# peaks_v30.net
KiCad netlist of a schematic drawn in EAGLE
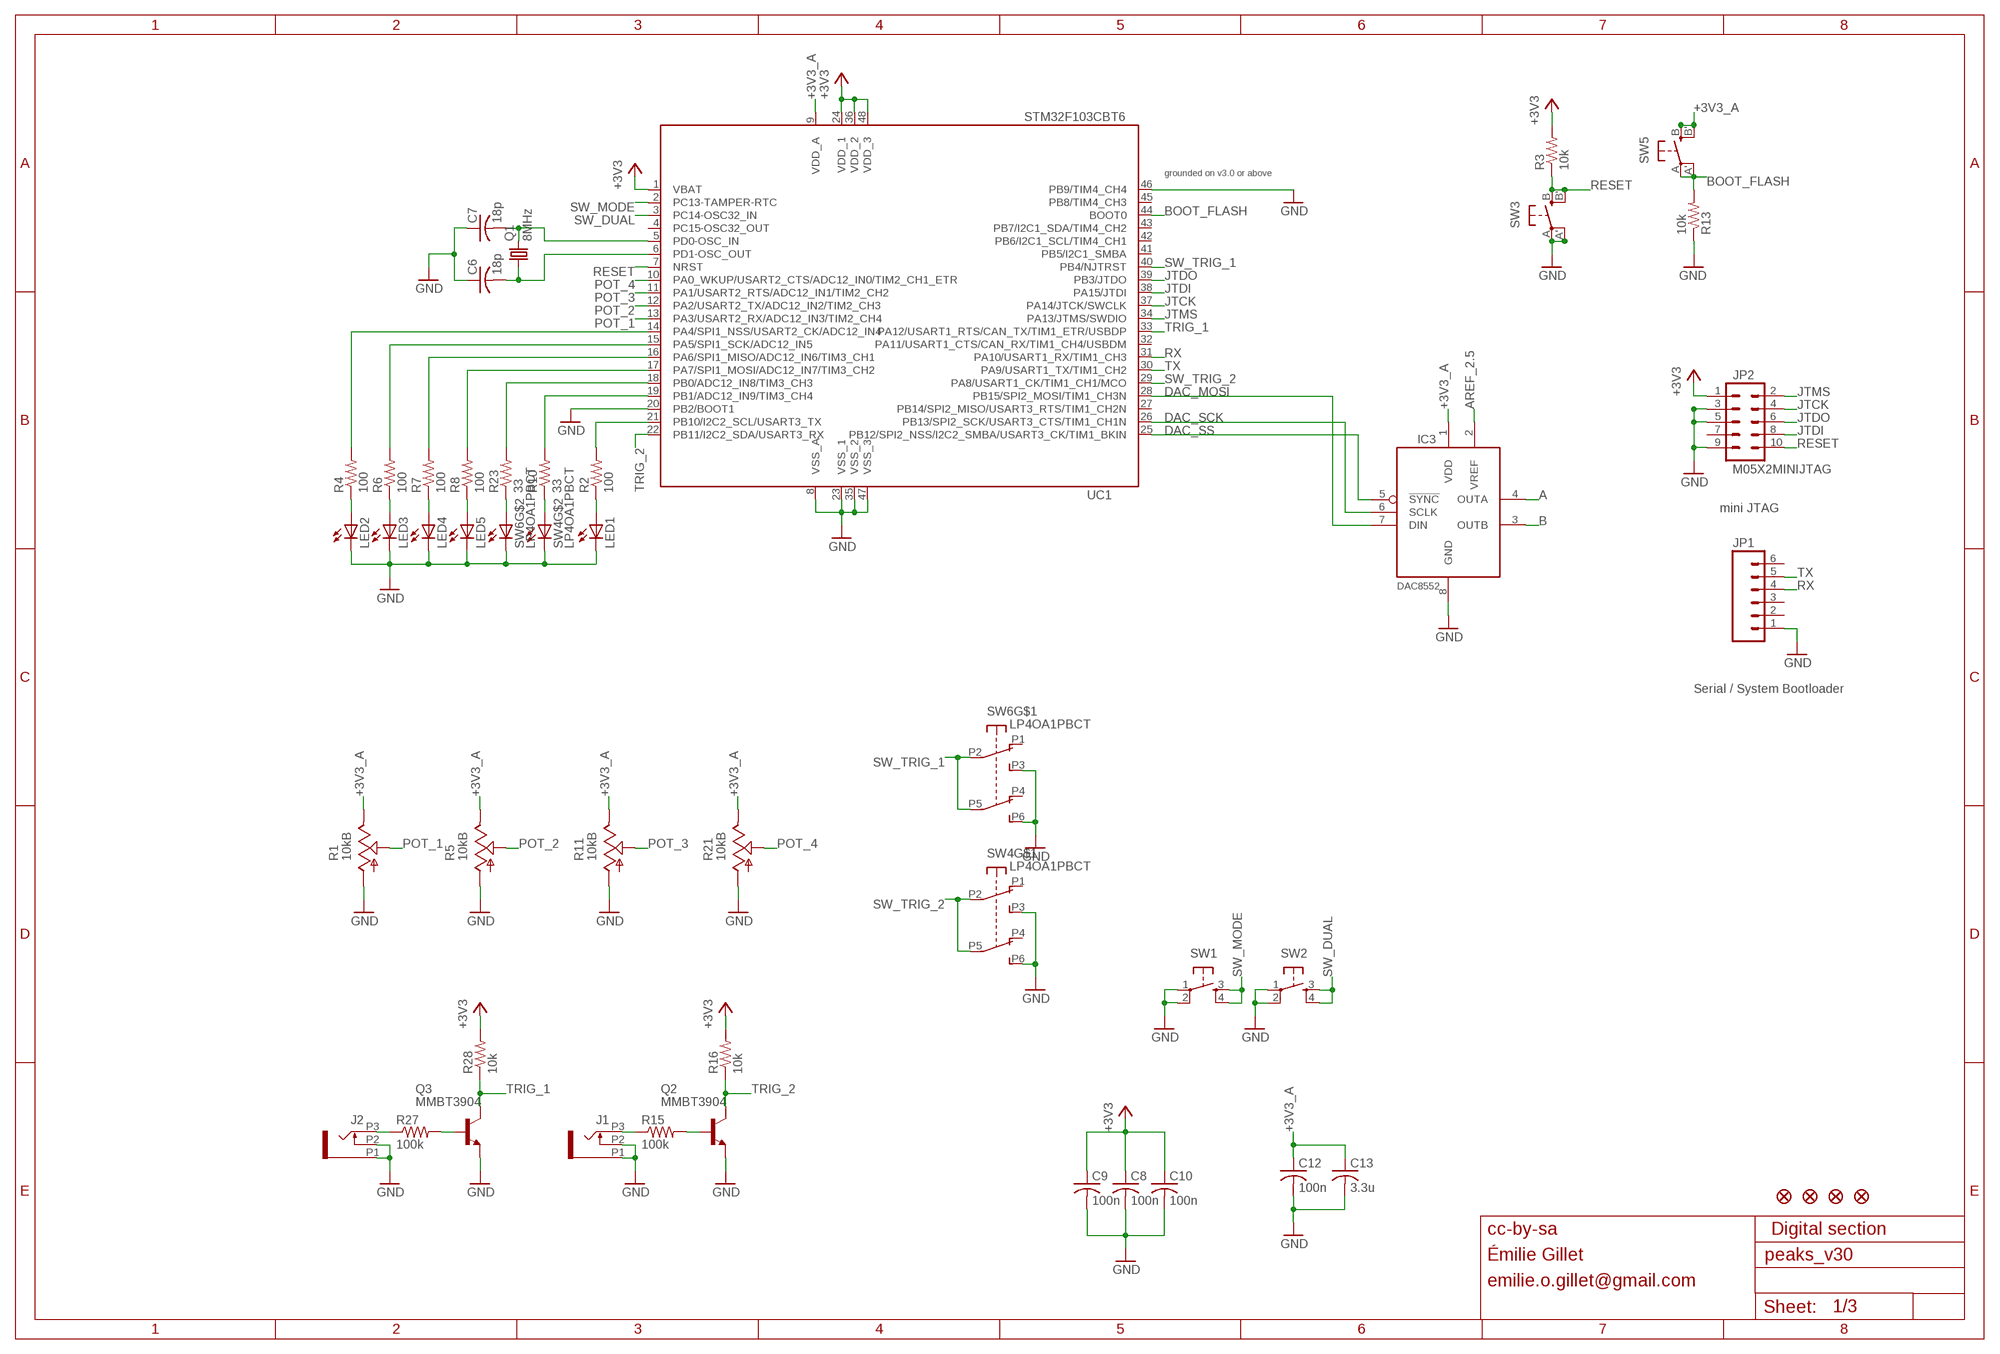
[diagram p0: schematic, sheet 1]
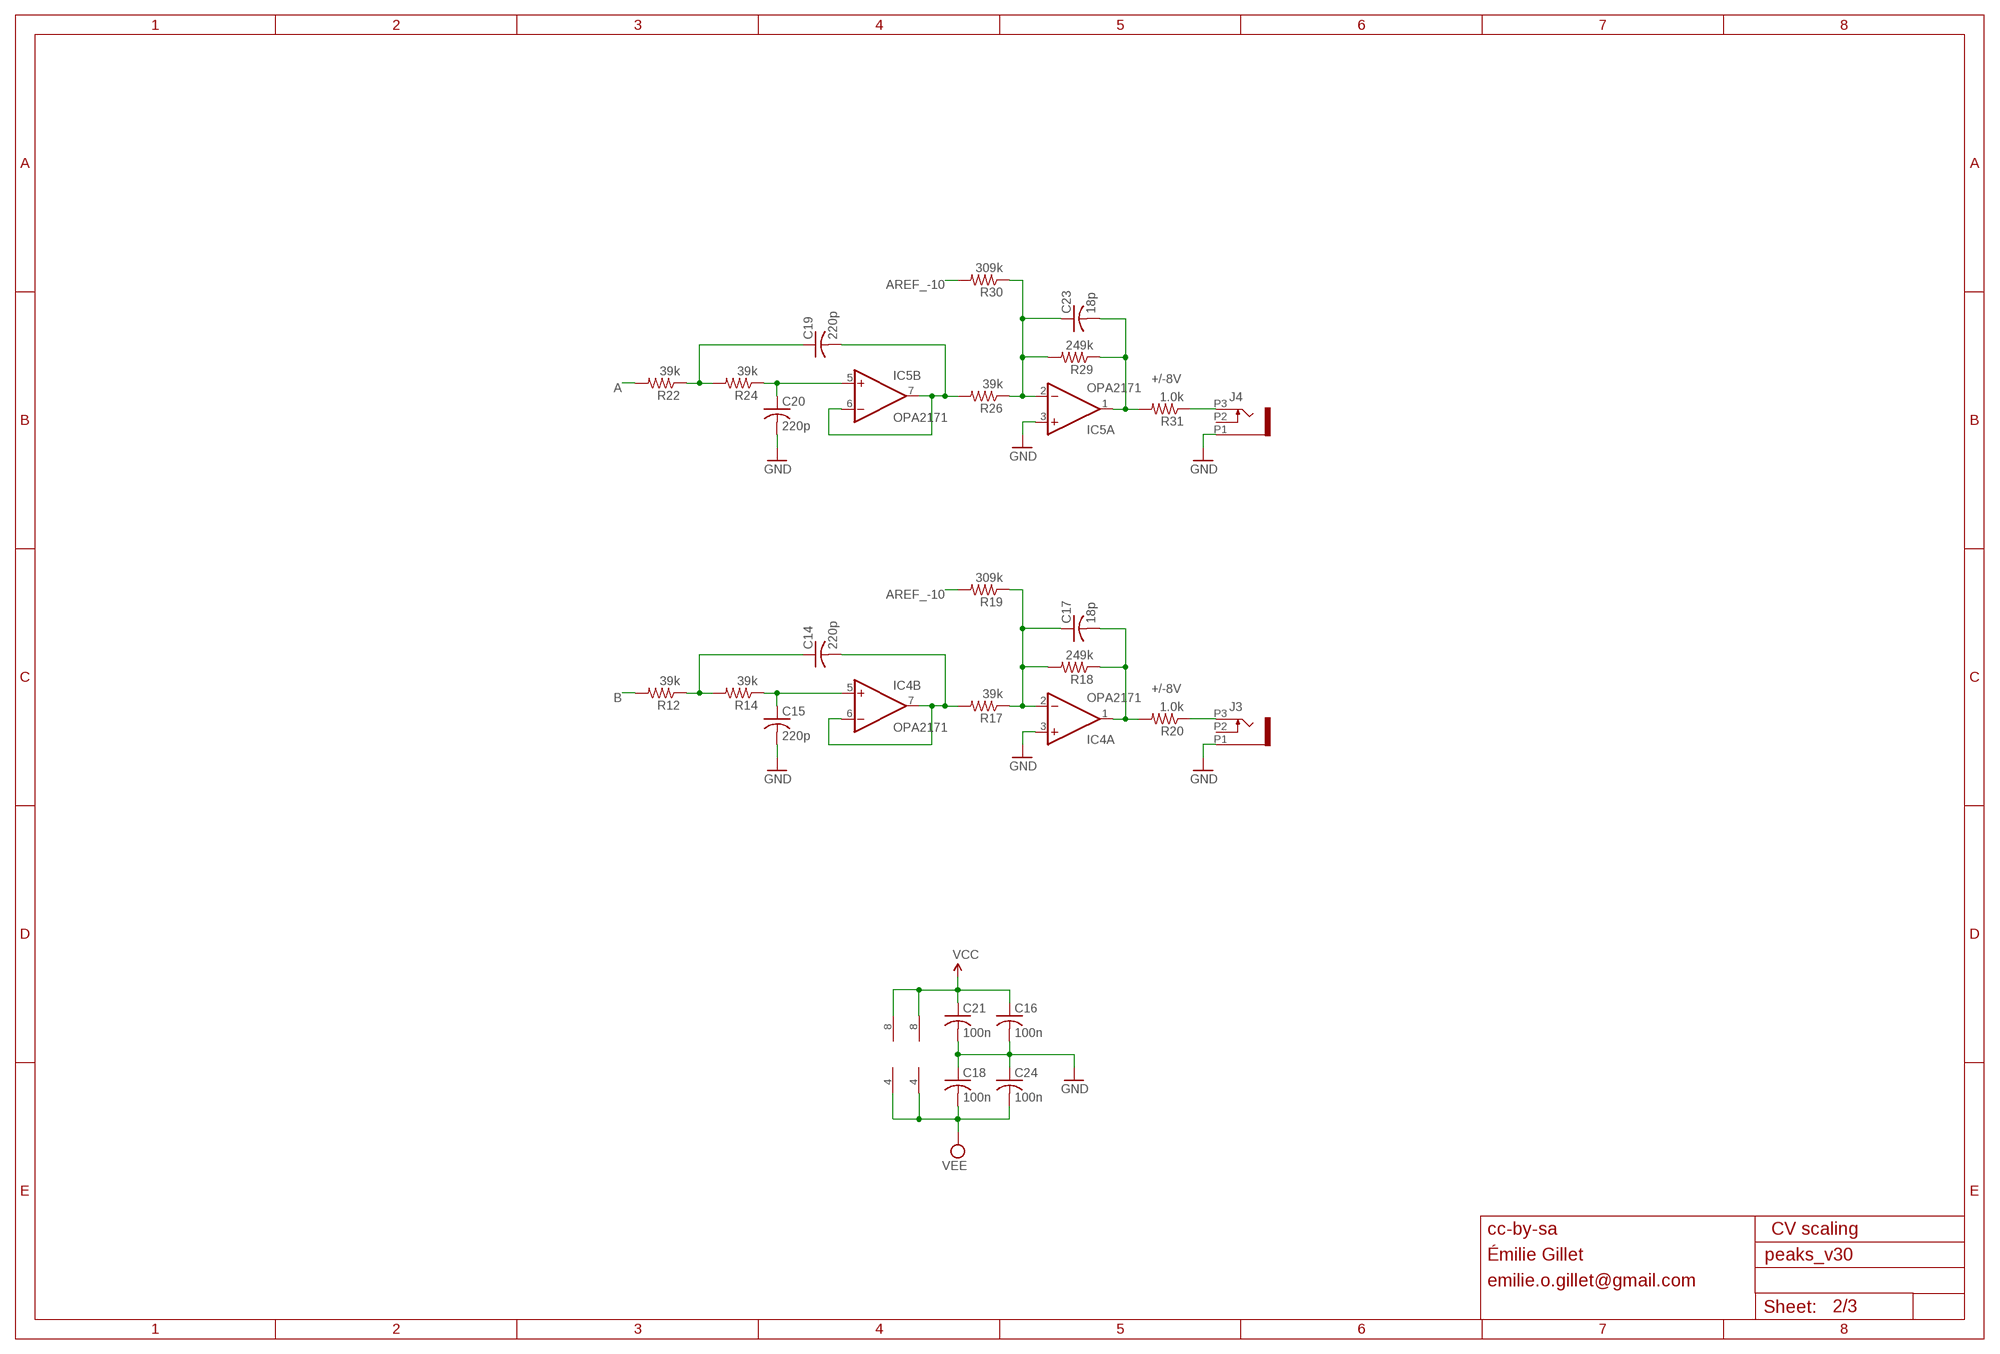
[diagram p1: schematic, sheet 2]
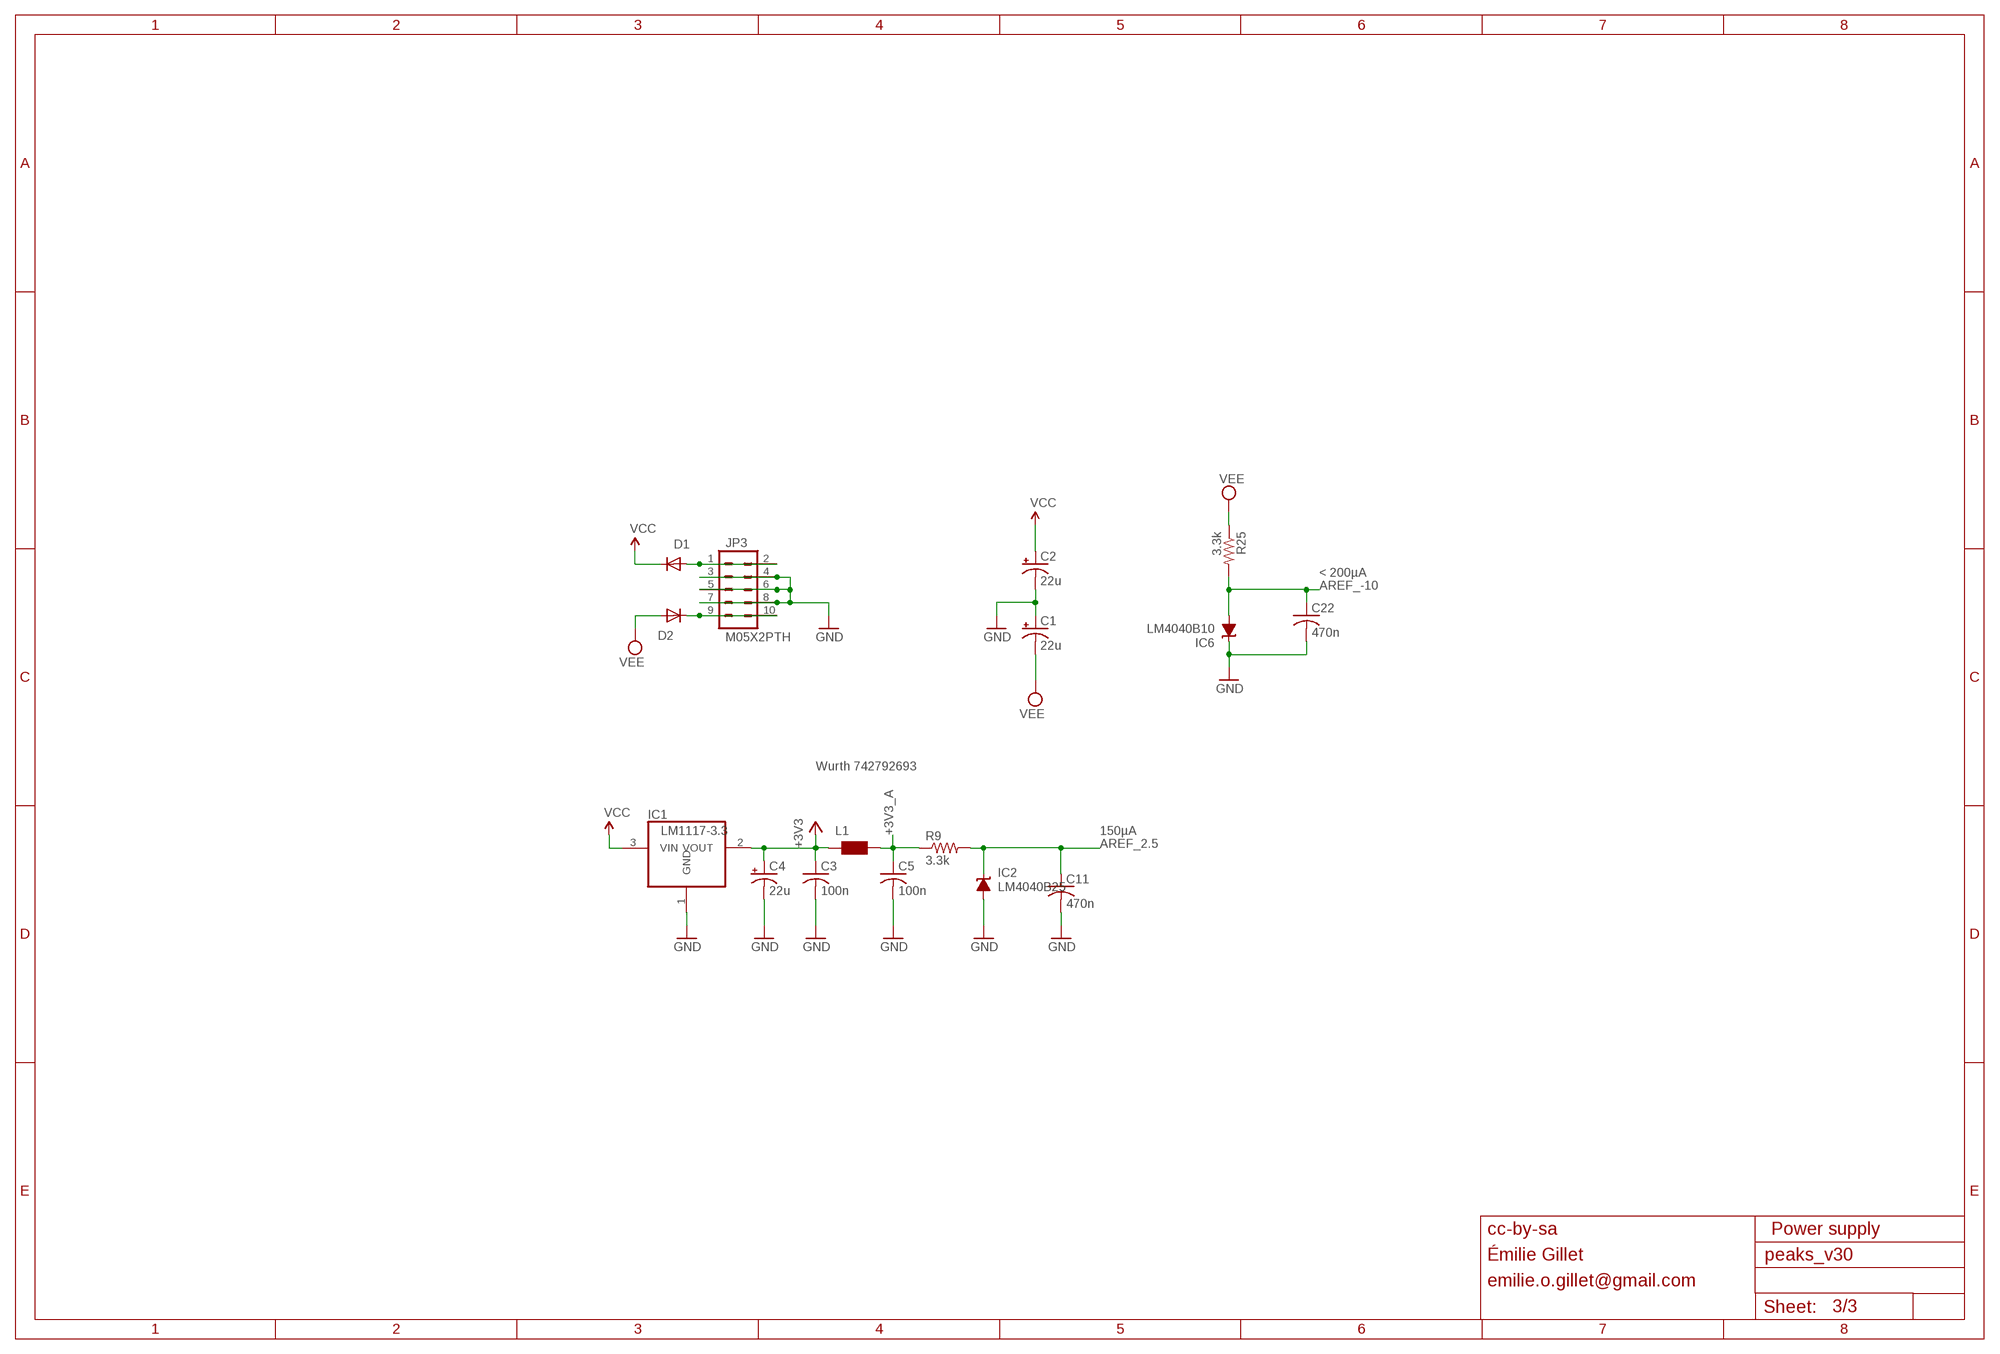
[diagram p2: schematic, sheet 3]

(export (version "E")
  (design (tool "Eeschema 10.0.6"))
  (components
    (comp (ref "C6")
      (value "18p")
      (footprint "eagle-import:C0603")
      (libsource (lib "eagle-import") (part "C-USC0603"))
    )
    (comp (ref "C7")
      (value "18p")
      (footprint "eagle-import:C0603")
      (libsource (lib "eagle-import") (part "C-USC0603"))
    )
    (comp (ref "C8")
      (value "100n")
      (footprint "eagle-import:C0603")
      (libsource (lib "eagle-import") (part "C-USC0603"))
    )
    (comp (ref "C9")
      (value "100n")
      (footprint "eagle-import:C0603")
      (libsource (lib "eagle-import") (part "C-USC0603"))
    )
    (comp (ref "C10")
      (value "100n")
      (footprint "eagle-import:C0603")
      (libsource (lib "eagle-import") (part "C-USC0603"))
    )
    (comp (ref "C12")
      (value "100n")
      (footprint "eagle-import:C0603")
      (libsource (lib "eagle-import") (part "C-USC0603"))
    )
    (comp (ref "C13")
      (value "3.3u")
      (footprint "eagle-import:C0603")
      (libsource (lib "eagle-import") (part "C-USC0603"))
    )
    (comp (ref "F1")
      (value "FIDUCIAL1X2")
      (footprint "eagle-import:FIDUCIAL-1X2")
      (libsource (lib "eagle-import") (part "FIDUCIAL1X2"))
    )
    (comp (ref "F2")
      (value "FIDUCIAL1X2")
      (footprint "eagle-import:FIDUCIAL-1X2")
      (libsource (lib "eagle-import") (part "FIDUCIAL1X2"))
    )
    (comp (ref "F3")
      (value "FIDUCIAL1X2")
      (footprint "eagle-import:FIDUCIAL-1X2")
      (libsource (lib "eagle-import") (part "FIDUCIAL1X2"))
    )
    (comp (ref "F4")
      (value "FIDUCIAL1X2")
      (footprint "eagle-import:FIDUCIAL-1X2")
      (libsource (lib "eagle-import") (part "FIDUCIAL1X2"))
    )
    (comp (ref "IC3")
      (value "DAC8552")
      (footprint "eagle-import:MSOP-8")
      (libsource (lib "eagle-import") (part "DAC8552"))
    )
    (comp (ref "J1")
      (value "PJ301_THONKICONN6")
      (footprint "eagle-import:WQP_PJ_301M6")
      (libsource (lib "eagle-import") (part "PJ301_THONKICONN6"))
    )
    (comp (ref "J2")
      (value "PJ301_THONKICONN6")
      (footprint "eagle-import:WQP_PJ_301M6")
      (libsource (lib "eagle-import") (part "PJ301_THONKICONN6"))
    )
    (comp (ref "JP1")
      (value "M06SIP")
      (footprint "eagle-import:1X06")
      (libsource (lib "eagle-import") (part "M06SIP"))
    )
    (comp (ref "JP2")
      (value "M05X2MINIJTAG")
      (footprint "eagle-import:2X5-1.27")
      (libsource (lib "eagle-import") (part "M05X2MINIJTAG"))
    )
    (comp (ref "LED1")
      (value "LED3MM")
      (footprint "eagle-import:LED3MM")
      (libsource (lib "eagle-import") (part "LED3MM"))
    )
    (comp (ref "LED2")
      (value "LED3MM")
      (footprint "eagle-import:LED3MM")
      (libsource (lib "eagle-import") (part "LED3MM"))
    )
    (comp (ref "LED3")
      (value "LED3MM")
      (footprint "eagle-import:LED3MM")
      (libsource (lib "eagle-import") (part "LED3MM"))
    )
    (comp (ref "LED4")
      (value "LED3MM")
      (footprint "eagle-import:LED3MM")
      (libsource (lib "eagle-import") (part "LED3MM"))
    )
    (comp (ref "LED5")
      (value "LED3MM")
      (footprint "eagle-import:LED3MM")
      (libsource (lib "eagle-import") (part "LED3MM"))
    )
    (comp (ref "Q1")
      (value "8MHz")
      (footprint "eagle-import:HC49UP")
      (libsource (lib "eagle-import") (part "CRYSTALHC49UP"))
    )
    (comp (ref "Q2")
      (value "MMBT3904")
      (footprint "eagle-import:SOT23-BEC")
      (libsource (lib "eagle-import") (part "-NPN-SOT23-BECMMBT3904LT1"))
    )
    (comp (ref "Q3")
      (value "MMBT3904")
      (footprint "eagle-import:SOT23-BEC")
      (libsource (lib "eagle-import") (part "-NPN-SOT23-BECMMBT3904LT1"))
    )
    (comp (ref "R1")
      (value "10kB")
      (footprint "eagle-import:ALPS_POT_VERTICAL_PS")
      (libsource (lib "eagle-import") (part "POT_USVERTICAL_PS"))
    )
    (comp (ref "R2")
      (value "100")
      (footprint "eagle-import:R0603")
      (libsource (lib "eagle-import") (part "R-US_R0603"))
    )
    (comp (ref "R3")
      (value "10k")
      (footprint "eagle-import:R0603")
      (libsource (lib "eagle-import") (part "R-US_R0603"))
    )
    (comp (ref "R4")
      (value "100")
      (footprint "eagle-import:R0603")
      (libsource (lib "eagle-import") (part "R-US_R0603"))
    )
    (comp (ref "R5")
      (value "10kB")
      (footprint "eagle-import:ALPS_POT_VERTICAL_PS")
      (libsource (lib "eagle-import") (part "POT_USVERTICAL_PS"))
    )
    (comp (ref "R6")
      (value "100")
      (footprint "eagle-import:R0603")
      (libsource (lib "eagle-import") (part "R-US_R0603"))
    )
    (comp (ref "R7")
      (value "100")
      (footprint "eagle-import:R0603")
      (libsource (lib "eagle-import") (part "R-US_R0603"))
    )
    (comp (ref "R8")
      (value "100")
      (footprint "eagle-import:R0603")
      (libsource (lib "eagle-import") (part "R-US_R0603"))
    )
    (comp (ref "R10")
      (value "33")
      (footprint "eagle-import:R0603")
      (libsource (lib "eagle-import") (part "R-US_R0603"))
    )
    (comp (ref "R11")
      (value "10kB")
      (footprint "eagle-import:ALPS_POT_VERTICAL_PS")
      (libsource (lib "eagle-import") (part "POT_USVERTICAL_PS"))
    )
    (comp (ref "R13")
      (value "10k")
      (footprint "eagle-import:R0603")
      (libsource (lib "eagle-import") (part "R-US_R0603"))
    )
    (comp (ref "R15")
      (value "100k")
      (footprint "eagle-import:R0603")
      (libsource (lib "eagle-import") (part "R-US_R0603"))
    )
    (comp (ref "R16")
      (value "10k")
      (footprint "eagle-import:R0603")
      (libsource (lib "eagle-import") (part "R-US_R0603"))
    )
    (comp (ref "R21")
      (value "10kB")
      (footprint "eagle-import:ALPS_POT_VERTICAL_PS")
      (libsource (lib "eagle-import") (part "POT_USVERTICAL_PS"))
    )
    (comp (ref "R23")
      (value "33")
      (footprint "eagle-import:R0603")
      (libsource (lib "eagle-import") (part "R-US_R0603"))
    )
    (comp (ref "R27")
      (value "100k")
      (footprint "eagle-import:R0603")
      (libsource (lib "eagle-import") (part "R-US_R0603"))
    )
    (comp (ref "R28")
      (value "10k")
      (footprint "eagle-import:R0603")
      (libsource (lib "eagle-import") (part "R-US_R0603"))
    )
    (comp (ref "SW1")
      (value "TAC_SWITCHPTH")
      (footprint "eagle-import:TACTILE-PTH")
      (libsource (lib "eagle-import") (part "TAC_SWITCHPTH"))
    )
    (comp (ref "SW2")
      (value "TAC_SWITCHPTH")
      (footprint "eagle-import:TACTILE-PTH")
      (libsource (lib "eagle-import") (part "TAC_SWITCHPTH"))
    )
    (comp (ref "SW3")
      (value "EVQQ2")
      (footprint "eagle-import:EVQ-Q2")
      (libsource (lib "eagle-import") (part "EVQQ2"))
    )
    (comp (ref "SW4")
      (value "LP4OA1PBCT")
      (footprint "eagle-import:LP4OA1PBCT")
      (libsource (lib "eagle-import") (part "LP4OA1PBCT"))
    )
    (comp (ref "SW5")
      (value "EVQQ2")
      (footprint "eagle-import:EVQ-Q2")
      (libsource (lib "eagle-import") (part "EVQQ2"))
    )
    (comp (ref "SW6")
      (value "LP4OA1PBCT")
      (footprint "eagle-import:LP4OA1PBCT")
      (libsource (lib "eagle-import") (part "LP4OA1PBCT"))
    )
    (comp (ref "UC1")
      (value "STM32F103CBT6")
      (footprint "eagle-import:LQFP48")
      (libsource (lib "eagle-import") (part "STM32F103CB"))
    )
    (comp (ref "C14")
      (value "220p")
      (footprint "eagle-import:C0603")
      (libsource (lib "eagle-import") (part "C-USC0603"))
    )
    (comp (ref "C15")
      (value "220p")
      (footprint "eagle-import:C0603")
      (libsource (lib "eagle-import") (part "C-USC0603"))
    )
    (comp (ref "C16")
      (value "100n")
      (footprint "eagle-import:C0603")
      (libsource (lib "eagle-import") (part "C-USC0603"))
    )
    (comp (ref "C17")
      (value "18p")
      (footprint "eagle-import:C0603")
      (libsource (lib "eagle-import") (part "C-USC0603"))
    )
    (comp (ref "C18")
      (value "100n")
      (footprint "eagle-import:C0603")
      (libsource (lib "eagle-import") (part "C-USC0603"))
    )
    (comp (ref "C19")
      (value "220p")
      (footprint "eagle-import:C0603")
      (libsource (lib "eagle-import") (part "C-USC0603"))
    )
    (comp (ref "C20")
      (value "220p")
      (footprint "eagle-import:C0603")
      (libsource (lib "eagle-import") (part "C-USC0603"))
    )
    (comp (ref "C21")
      (value "100n")
      (footprint "eagle-import:C0603")
      (libsource (lib "eagle-import") (part "C-USC0603"))
    )
    (comp (ref "C23")
      (value "18p")
      (footprint "eagle-import:C0603")
      (libsource (lib "eagle-import") (part "C-USC0603"))
    )
    (comp (ref "C24")
      (value "100n")
      (footprint "eagle-import:C0603")
      (libsource (lib "eagle-import") (part "C-USC0603"))
    )
    (comp (ref "IC4")
      (value "OPA2171")
      (footprint "eagle-import:SO08")
      (libsource (lib "eagle-import") (part "TL072D"))
    )
    (comp (ref "IC5")
      (value "OPA2171")
      (footprint "eagle-import:SO08")
      (libsource (lib "eagle-import") (part "TL072D"))
    )
    (comp (ref "J3")
      (value "PJ301_THONKICONN6")
      (footprint "eagle-import:WQP_PJ_301M6")
      (libsource (lib "eagle-import") (part "PJ301_THONKICONN6"))
    )
    (comp (ref "J4")
      (value "PJ301_THONKICONN6")
      (footprint "eagle-import:WQP_PJ_301M6")
      (libsource (lib "eagle-import") (part "PJ301_THONKICONN6"))
    )
    (comp (ref "R12")
      (value "39k")
      (footprint "eagle-import:R0603")
      (libsource (lib "eagle-import") (part "R-US_R0603"))
    )
    (comp (ref "R14")
      (value "39k")
      (footprint "eagle-import:R0603")
      (libsource (lib "eagle-import") (part "R-US_R0603"))
    )
    (comp (ref "R17")
      (value "39k")
      (footprint "eagle-import:R0603")
      (libsource (lib "eagle-import") (part "R-US_R0603"))
    )
    (comp (ref "R18")
      (value "249k")
      (footprint "eagle-import:R0603")
      (libsource (lib "eagle-import") (part "R-US_R0603"))
    )
    (comp (ref "R19")
      (value "309k")
      (footprint "eagle-import:R0603")
      (libsource (lib "eagle-import") (part "R-US_R0603"))
    )
    (comp (ref "R20")
      (value "1.0k")
      (footprint "eagle-import:R0603")
      (libsource (lib "eagle-import") (part "R-US_R0603"))
    )
    (comp (ref "R22")
      (value "39k")
      (footprint "eagle-import:R0603")
      (libsource (lib "eagle-import") (part "R-US_R0603"))
    )
    (comp (ref "R24")
      (value "39k")
      (footprint "eagle-import:R0603")
      (libsource (lib "eagle-import") (part "R-US_R0603"))
    )
    (comp (ref "R26")
      (value "39k")
      (footprint "eagle-import:R0603")
      (libsource (lib "eagle-import") (part "R-US_R0603"))
    )
    (comp (ref "R29")
      (value "249k")
      (footprint "eagle-import:R0603")
      (libsource (lib "eagle-import") (part "R-US_R0603"))
    )
    (comp (ref "R30")
      (value "309k")
      (footprint "eagle-import:R0603")
      (libsource (lib "eagle-import") (part "R-US_R0603"))
    )
    (comp (ref "R31")
      (value "1.0k")
      (footprint "eagle-import:R0603")
      (libsource (lib "eagle-import") (part "R-US_R0603"))
    )
    (comp (ref "C1")
      (value "22u")
      (footprint "eagle-import:PANASONIC_C")
      (libsource (lib "eagle-import") (part "CPOL-USC"))
    )
    (comp (ref "C2")
      (value "22u")
      (footprint "eagle-import:PANASONIC_C")
      (libsource (lib "eagle-import") (part "CPOL-USC"))
    )
    (comp (ref "C3")
      (value "100n")
      (footprint "eagle-import:C0603")
      (libsource (lib "eagle-import") (part "C-USC0603"))
    )
    (comp (ref "C4")
      (value "22u")
      (footprint "eagle-import:PANASONIC_C")
      (libsource (lib "eagle-import") (part "CPOL-USC"))
    )
    (comp (ref "C5")
      (value "100n")
      (footprint "eagle-import:C0603")
      (libsource (lib "eagle-import") (part "C-USC0603"))
    )
    (comp (ref "C11")
      (value "470n")
      (footprint "eagle-import:C0603")
      (libsource (lib "eagle-import") (part "C-USC0603"))
    )
    (comp (ref "C22")
      (value "470n")
      (footprint "eagle-import:C0603")
      (libsource (lib "eagle-import") (part "C-USC0603"))
    )
    (comp (ref "D1")
      (value "1N5819HW")
      (footprint "eagle-import:SOD123")
      (libsource (lib "eagle-import") (part "DIODE-SOD123"))
    )
    (comp (ref "D2")
      (value "1N5819HW")
      (footprint "eagle-import:SOD123")
      (libsource (lib "eagle-import") (part "DIODE-SOD123"))
    )
    (comp (ref "IC1")
      (value "LM1117-3.3")
      (footprint "eagle-import:SOT223")
      (libsource (lib "eagle-import") (part "REG1117"))
    )
    (comp (ref "IC2")
      (value "LM4040B25")
      (footprint "eagle-import:DBZ_R-PDSO-G3")
      (libsource (lib "eagle-import") (part "LM4041DBZB12"))
    )
    (comp (ref "IC6")
      (value "LM4040B10")
      (footprint "eagle-import:DBZ_R-PDSO-G3")
      (libsource (lib "eagle-import") (part "LM4041DBZB12"))
    )
    (comp (ref "JP3")
      (value "M05X2PTH")
      (footprint "eagle-import:AVR_ICSP")
      (libsource (lib "eagle-import") (part "M05X2PTH"))
    )
    (comp (ref "L1")
      (value "WE-CBF_0603")
      (footprint "eagle-import:0603")
      (libsource (lib "eagle-import") (part "WE-CBF_0603"))
    )
    (comp (ref "R9")
      (value "3.3k")
      (footprint "eagle-import:R0603")
      (libsource (lib "eagle-import") (part "R-US_R0603"))
    )
    (comp (ref "R25")
      (value "3.3k")
      (footprint "eagle-import:R0603")
      (libsource (lib "eagle-import") (part "R-US_R0603"))
    )
  )
  (nets
    (net (code "1") (name "+3V3") (class "Default")
      (node (ref "C10") (pin "1") (pinfunction "1_1") (pintype "passive"))
      (node (ref "C3") (pin "1") (pinfunction "1_1") (pintype "passive"))
      (node (ref "C4") (pin "+") (pinfunction "+_+") (pintype "passive"))
      (node (ref "C8") (pin "1") (pinfunction "1_1") (pintype "passive"))
      (node (ref "C9") (pin "1") (pinfunction "1_1") (pintype "passive"))
      (node (ref "IC1") (pin "2") (pinfunction "VOUT_2") (pintype "output"))
      (node (ref "JP2") (pin "1") (pinfunction "1_1") (pintype "passive"))
      (node (ref "L1") (pin "1") (pinfunction "1_1") (pintype "passive"))
      (node (ref "R16") (pin "2") (pinfunction "2_2") (pintype "passive"))
      (node (ref "R28") (pin "2") (pinfunction "2_2") (pintype "passive"))
      (node (ref "R3") (pin "2") (pinfunction "2_2") (pintype "passive"))
      (node (ref "UC1") (pin "1") (pinfunction "VBAT_1") (pintype "power_in"))
      (node (ref "UC1") (pin "24") (pinfunction "VDD_1_24") (pintype "power_in"))
      (node (ref "UC1") (pin "36") (pinfunction "VDD_2_36") (pintype "power_in"))
      (node (ref "UC1") (pin "48") (pinfunction "VDD_3_48") (pintype "power_in"))
    )
    (net (code "2") (name "+3V3_A") (class "Default")
      (node (ref "C12") (pin "1") (pinfunction "1_1") (pintype "passive"))
      (node (ref "C13") (pin "1") (pinfunction "1_1") (pintype "passive"))
      (node (ref "C5") (pin "1") (pinfunction "1_1") (pintype "passive"))
      (node (ref "IC3") (pin "1") (pinfunction "VDD_1") (pintype "power_in"))
      (node (ref "L1") (pin "2") (pinfunction "2_2") (pintype "passive"))
      (node (ref "R1") (pin "P$1") (pinfunction "E_P$1") (pintype "passive"))
      (node (ref "R11") (pin "P$1") (pinfunction "E_P$1") (pintype "passive"))
      (node (ref "R21") (pin "P$1") (pinfunction "E_P$1") (pintype "passive"))
      (node (ref "R5") (pin "P$1") (pinfunction "E_P$1") (pintype "passive"))
      (node (ref "R9") (pin "1") (pinfunction "1_1") (pintype "passive"))
      (node (ref "SW5") (pin "B") (pinfunction "S_B") (pintype "passive"))
      (node (ref "SW5") (pin "B'") (pinfunction "S1_B'") (pintype "passive"))
      (node (ref "UC1") (pin "9") (pinfunction "VDD_A_9") (pintype "power_in"))
    )
    (net (code "3") (name "A") (class "Default")
      (node (ref "IC3") (pin "4") (pinfunction "OUTA_4") (pintype "output"))
      (node (ref "R22") (pin "2") (pinfunction "2_2") (pintype "passive"))
    )
    (net (code "4") (name "AREF_-10") (class "Default")
      (node (ref "C22") (pin "1") (pinfunction "1_1") (pintype "passive"))
      (node (ref "IC6") (pin "2") (pinfunction "A_2") (pintype "passive"))
      (node (ref "R19") (pin "2") (pinfunction "2_2") (pintype "passive"))
      (node (ref "R25") (pin "2") (pinfunction "2_2") (pintype "passive"))
      (node (ref "R30") (pin "2") (pinfunction "2_2") (pintype "passive"))
    )
    (net (code "5") (name "AREF_2.5") (class "Default")
      (node (ref "C11") (pin "1") (pinfunction "1_1") (pintype "passive"))
      (node (ref "IC2") (pin "1") (pinfunction "C_1") (pintype "passive"))
      (node (ref "IC3") (pin "2") (pinfunction "VREF_2") (pintype "power_in"))
      (node (ref "R9") (pin "2") (pinfunction "2_2") (pintype "passive"))
    )
    (net (code "6") (name "B") (class "Default")
      (node (ref "IC3") (pin "3") (pinfunction "OUTB_3") (pintype "input"))
      (node (ref "R12") (pin "2") (pinfunction "2_2") (pintype "passive"))
    )
    (net (code "7") (name "BOOT_FLASH") (class "Default")
      (node (ref "R13") (pin "2") (pinfunction "2_2") (pintype "passive"))
      (node (ref "SW5") (pin "A") (pinfunction "P_A") (pintype "passive"))
      (node (ref "SW5") (pin "A'") (pinfunction "P1_A'") (pintype "passive"))
      (node (ref "UC1") (pin "44") (pinfunction "BOOT0_44") (pintype "input"))
    )
    (net (code "8") (name "DAC_MOSI") (class "Default")
      (node (ref "IC3") (pin "7") (pinfunction "DIN_7") (pintype "bidirectional"))
      (node (ref "UC1") (pin "28") (pinfunction "PB15/SPI2_MOSI/TIM1_CH3N_28") (pintype "input"))
    )
    (net (code "9") (name "DAC_SCK") (class "Default")
      (node (ref "IC3") (pin "6") (pinfunction "SCLK_6") (pintype "bidirectional"))
      (node (ref "UC1") (pin "26") (pinfunction "PB13/SPI2_SCK/USART3_CTS/TIM1_CH1N_26") (pintype "input"))
    )
    (net (code "10") (name "DAC_SS") (class "Default")
      (node (ref "IC3") (pin "5") (pinfunction "~{SYNC}_5") (pintype "bidirectional"))
      (node (ref "UC1") (pin "25") (pinfunction "PB12/SPI2_NSS/I2C2_SMBA/USART3_CK/TIM1_BKIN_25") (pintype "input"))
    )
    (net (code "11") (name "GND") (class "Default")
      (node (ref "C1") (pin "+") (pinfunction "+_+") (pintype "passive"))
      (node (ref "C10") (pin "2") (pinfunction "2_2") (pintype "passive"))
      (node (ref "C11") (pin "2") (pinfunction "2_2") (pintype "passive"))
      (node (ref "C12") (pin "2") (pinfunction "2_2") (pintype "passive"))
      (node (ref "C13") (pin "2") (pinfunction "2_2") (pintype "passive"))
      (node (ref "C15") (pin "2") (pinfunction "2_2") (pintype "passive"))
      (node (ref "C16") (pin "2") (pinfunction "2_2") (pintype "passive"))
      (node (ref "C18") (pin "1") (pinfunction "1_1") (pintype "passive"))
      (node (ref "C2") (pin "-") (pinfunction "-_-") (pintype "passive"))
      (node (ref "C20") (pin "2") (pinfunction "2_2") (pintype "passive"))
      (node (ref "C21") (pin "2") (pinfunction "2_2") (pintype "passive"))
      (node (ref "C22") (pin "2") (pinfunction "2_2") (pintype "passive"))
      (node (ref "C24") (pin "1") (pinfunction "1_1") (pintype "passive"))
      (node (ref "C3") (pin "2") (pinfunction "2_2") (pintype "passive"))
      (node (ref "C4") (pin "-") (pinfunction "-_-") (pintype "passive"))
      (node (ref "C5") (pin "2") (pinfunction "2_2") (pintype "passive"))
      (node (ref "C6") (pin "1") (pinfunction "1_1") (pintype "passive"))
      (node (ref "C7") (pin "1") (pinfunction "1_1") (pintype "passive"))
      (node (ref "C8") (pin "2") (pinfunction "2_2") (pintype "passive"))
      (node (ref "C9") (pin "2") (pinfunction "2_2") (pintype "passive"))
      (node (ref "IC1") (pin "1") (pinfunction "GND_1") (pintype "power_in"))
      (node (ref "IC2") (pin "2") (pinfunction "A_2") (pintype "passive"))
      (node (ref "IC3") (pin "8") (pinfunction "GND_8") (pintype "power_in"))
      (node (ref "IC4") (pin "3") (pinfunction "+IN_3") (pintype "input"))
      (node (ref "IC5") (pin "3") (pinfunction "+IN_3") (pintype "input"))
      (node (ref "IC6") (pin "1") (pinfunction "C_1") (pintype "passive"))
      (node (ref "J1") (pin "P1") (pinfunction "1_P1") (pintype "passive"))
      (node (ref "J1") (pin "P2") (pinfunction "2_P2") (pintype "passive"))
      (node (ref "J2") (pin "P1") (pinfunction "1_P1") (pintype "passive"))
      (node (ref "J2") (pin "P2") (pinfunction "2_P2") (pintype "passive"))
      (node (ref "J3") (pin "P1") (pinfunction "1_P1") (pintype "passive"))
      (node (ref "J4") (pin "P1") (pinfunction "1_P1") (pintype "passive"))
      (node (ref "JP1") (pin "1") (pinfunction "1_1") (pintype "passive"))
      (node (ref "JP2") (pin "3") (pinfunction "3_3") (pintype "passive"))
      (node (ref "JP2") (pin "5") (pinfunction "5_5") (pintype "passive"))
      (node (ref "JP2") (pin "9") (pinfunction "9_9") (pintype "passive"))
      (node (ref "JP3") (pin "3") (pinfunction "3_3") (pintype "passive"))
      (node (ref "JP3") (pin "4") (pinfunction "4_4") (pintype "passive"))
      (node (ref "JP3") (pin "5") (pinfunction "5_5") (pintype "passive"))
      (node (ref "JP3") (pin "6") (pinfunction "6_6") (pintype "passive"))
      (node (ref "JP3") (pin "7") (pinfunction "7_7") (pintype "passive"))
      (node (ref "JP3") (pin "8") (pinfunction "8_8") (pintype "passive"))
      (node (ref "LED1") (pin "K") (pinfunction "C_K") (pintype "passive"))
      (node (ref "LED2") (pin "K") (pinfunction "C_K") (pintype "passive"))
      (node (ref "LED3") (pin "K") (pinfunction "C_K") (pintype "passive"))
      (node (ref "LED4") (pin "K") (pinfunction "C_K") (pintype "passive"))
      (node (ref "LED5") (pin "K") (pinfunction "C_K") (pintype "passive"))
      (node (ref "Q2") (pin "E") (pinfunction "E_E") (pintype "passive"))
      (node (ref "Q3") (pin "E") (pinfunction "E_E") (pintype "passive"))
      (node (ref "R1") (pin "P$3") (pinfunction "A_P$3") (pintype "passive"))
      (node (ref "R11") (pin "P$3") (pinfunction "A_P$3") (pintype "passive"))
      (node (ref "R13") (pin "1") (pinfunction "1_1") (pintype "passive"))
      (node (ref "R21") (pin "P$3") (pinfunction "A_P$3") (pintype "passive"))
      (node (ref "R5") (pin "P$3") (pinfunction "A_P$3") (pintype "passive"))
      (node (ref "SW1") (pin "1") (pinfunction "1_1") (pintype "passive"))
      (node (ref "SW1") (pin "2") (pinfunction "2_2") (pintype "passive"))
      (node (ref "SW2") (pin "1") (pinfunction "1_1") (pintype "passive"))
      (node (ref "SW2") (pin "2") (pinfunction "2_2") (pintype "passive"))
      (node (ref "SW3") (pin "A") (pinfunction "P_A") (pintype "passive"))
      (node (ref "SW3") (pin "A'") (pinfunction "P1_A'") (pintype "passive"))
      (node (ref "SW4") (pin "L2") (pinfunction "L2_L2") (pintype "passive"))
      (node (ref "SW4") (pin "P3") (pinfunction "A3_P3") (pintype "passive"))
      (node (ref "SW4") (pin "P6") (pinfunction "B3_P6") (pintype "passive"))
      (node (ref "SW6") (pin "L2") (pinfunction "L2_L2") (pintype "passive"))
      (node (ref "SW6") (pin "P3") (pinfunction "A3_P3") (pintype "passive"))
      (node (ref "SW6") (pin "P6") (pinfunction "B3_P6") (pintype "passive"))
      (node (ref "UC1") (pin "20") (pinfunction "PB2/BOOT1_20") (pintype "bidirectional"))
      (node (ref "UC1") (pin "23") (pinfunction "VSS_1_23") (pintype "power_in"))
      (node (ref "UC1") (pin "35") (pinfunction "VSS_2_35") (pintype "power_in"))
      (node (ref "UC1") (pin "46") (pinfunction "PB9/TIM4_CH4_46") (pintype "input"))
      (node (ref "UC1") (pin "47") (pinfunction "VSS_3_47") (pintype "power_in"))
      (node (ref "UC1") (pin "8") (pinfunction "VSS_A_8") (pintype "power_in"))
    )
    (net (code "12") (name "JTCK") (class "Default")
      (node (ref "JP2") (pin "4") (pinfunction "4_4") (pintype "passive"))
      (node (ref "UC1") (pin "37") (pinfunction "PA14/JTCK/SWCLK_37") (pintype "bidirectional"))
    )
    (net (code "13") (name "JTDI") (class "Default")
      (node (ref "JP2") (pin "8") (pinfunction "8_8") (pintype "passive"))
      (node (ref "UC1") (pin "38") (pinfunction "PA15/JTDI_38") (pintype "bidirectional"))
    )
    (net (code "14") (name "JTDO") (class "Default")
      (node (ref "JP2") (pin "6") (pinfunction "6_6") (pintype "passive"))
      (node (ref "UC1") (pin "39") (pinfunction "PB3/JTDO_39") (pintype "bidirectional"))
    )
    (net (code "15") (name "JTMS") (class "Default")
      (node (ref "JP2") (pin "2") (pinfunction "2_2") (pintype "passive"))
      (node (ref "UC1") (pin "34") (pinfunction "PA13/JTMS/SWDIO_34") (pintype "bidirectional"))
    )
    (net (code "16") (name "Net-(C14-Pad1)") (class "Default")
      (node (ref "C14") (pin "1") (pinfunction "1_1") (pintype "passive"))
      (node (ref "R12") (pin "1") (pinfunction "1_1") (pintype "passive"))
      (node (ref "R14") (pin "2") (pinfunction "2_2") (pintype "passive"))
    )
    (net (code "17") (name "Net-(C19-Pad1)") (class "Default")
      (node (ref "C19") (pin "1") (pinfunction "1_1") (pintype "passive"))
      (node (ref "R22") (pin "1") (pinfunction "1_1") (pintype "passive"))
      (node (ref "R24") (pin "2") (pinfunction "2_2") (pintype "passive"))
    )
    (net (code "18") (name "Net-(D1-PadA)") (class "Default")
      (node (ref "D1") (pin "A") (pinfunction "A_A") (pintype "passive"))
      (node (ref "JP3") (pin "1") (pinfunction "1_1") (pintype "passive"))
      (node (ref "JP3") (pin "2") (pinfunction "2_2") (pintype "passive"))
    )
    (net (code "19") (name "Net-(D2-PadC)") (class "Default")
      (node (ref "D2") (pin "C") (pinfunction "C_C") (pintype "passive"))
      (node (ref "JP3") (pin "10") (pinfunction "10_10") (pintype "passive"))
      (node (ref "JP3") (pin "9") (pinfunction "9_9") (pintype "passive"))
    )
    (net (code "20") (name "Net-(IC4A--IN)") (class "Default")
      (node (ref "C17") (pin "1") (pinfunction "1_1") (pintype "passive"))
      (node (ref "IC4") (pin "2") (pinfunction "-IN_2") (pintype "input"))
      (node (ref "R17") (pin "1") (pinfunction "1_1") (pintype "passive"))
      (node (ref "R18") (pin "2") (pinfunction "2_2") (pintype "passive"))
      (node (ref "R19") (pin "1") (pinfunction "1_1") (pintype "passive"))
    )
    (net (code "21") (name "Net-(IC4A-OUT)") (class "Default")
      (node (ref "C17") (pin "2") (pinfunction "2_2") (pintype "passive"))
      (node (ref "IC4") (pin "1") (pinfunction "OUT_1") (pintype "output"))
      (node (ref "R18") (pin "1") (pinfunction "1_1") (pintype "passive"))
      (node (ref "R20") (pin "2") (pinfunction "2_2") (pintype "passive"))
    )
    (net (code "22") (name "Net-(IC4B-+IN)") (class "Default")
      (node (ref "C15") (pin "1") (pinfunction "1_1") (pintype "passive"))
      (node (ref "IC4") (pin "5") (pinfunction "+IN_5") (pintype "input"))
      (node (ref "R14") (pin "1") (pinfunction "1_1") (pintype "passive"))
    )
    (net (code "23") (name "Net-(IC4B--IN)") (class "Default")
      (node (ref "C14") (pin "2") (pinfunction "2_2") (pintype "passive"))
      (node (ref "IC4") (pin "6") (pinfunction "-IN_6") (pintype "input"))
      (node (ref "IC4") (pin "7") (pinfunction "OUT_7") (pintype "output"))
      (node (ref "R17") (pin "2") (pinfunction "2_2") (pintype "passive"))
    )
    (net (code "24") (name "Net-(IC5A--IN)") (class "Default")
      (node (ref "C23") (pin "1") (pinfunction "1_1") (pintype "passive"))
      (node (ref "IC5") (pin "2") (pinfunction "-IN_2") (pintype "input"))
      (node (ref "R26") (pin "1") (pinfunction "1_1") (pintype "passive"))
      (node (ref "R29") (pin "2") (pinfunction "2_2") (pintype "passive"))
      (node (ref "R30") (pin "1") (pinfunction "1_1") (pintype "passive"))
    )
    (net (code "25") (name "Net-(IC5A-OUT)") (class "Default")
      (node (ref "C23") (pin "2") (pinfunction "2_2") (pintype "passive"))
      (node (ref "IC5") (pin "1") (pinfunction "OUT_1") (pintype "output"))
      (node (ref "R29") (pin "1") (pinfunction "1_1") (pintype "passive"))
      (node (ref "R31") (pin "2") (pinfunction "2_2") (pintype "passive"))
    )
    (net (code "26") (name "Net-(IC5B-+IN)") (class "Default")
      (node (ref "C20") (pin "1") (pinfunction "1_1") (pintype "passive"))
      (node (ref "IC5") (pin "5") (pinfunction "+IN_5") (pintype "input"))
      (node (ref "R24") (pin "1") (pinfunction "1_1") (pintype "passive"))
    )
    (net (code "27") (name "Net-(IC5B--IN)") (class "Default")
      (node (ref "C19") (pin "2") (pinfunction "2_2") (pintype "passive"))
      (node (ref "IC5") (pin "6") (pinfunction "-IN_6") (pintype "input"))
      (node (ref "IC5") (pin "7") (pinfunction "OUT_7") (pintype "output"))
      (node (ref "R26") (pin "2") (pinfunction "2_2") (pintype "passive"))
    )
    (net (code "28") (name "Net-(J1-3)") (class "Default")
      (node (ref "J1") (pin "P3") (pinfunction "3_P3") (pintype "passive"))
      (node (ref "R15") (pin "1") (pinfunction "1_1") (pintype "passive"))
    )
    (net (code "29") (name "Net-(J2-3)") (class "Default")
      (node (ref "J2") (pin "P3") (pinfunction "3_P3") (pintype "passive"))
      (node (ref "R27") (pin "1") (pinfunction "1_1") (pintype "passive"))
    )
    (net (code "30") (name "Net-(J3-3)") (class "Default")
      (node (ref "J3") (pin "P3") (pinfunction "3_P3") (pintype "passive"))
      (node (ref "R20") (pin "1") (pinfunction "1_1") (pintype "passive"))
    )
    (net (code "31") (name "Net-(J4-3)") (class "Default")
      (node (ref "J4") (pin "P3") (pinfunction "3_P3") (pintype "passive"))
      (node (ref "R31") (pin "1") (pinfunction "1_1") (pintype "passive"))
    )
    (net (code "32") (name "Net-(LED1-PadA)") (class "Default")
      (node (ref "LED1") (pin "A") (pinfunction "A_A") (pintype "passive"))
      (node (ref "R2") (pin "1") (pinfunction "1_1") (pintype "passive"))
    )
    (net (code "33") (name "Net-(LED2-PadA)") (class "Default")
      (node (ref "LED2") (pin "A") (pinfunction "A_A") (pintype "passive"))
      (node (ref "R4") (pin "1") (pinfunction "1_1") (pintype "passive"))
    )
    (net (code "34") (name "Net-(LED3-PadA)") (class "Default")
      (node (ref "LED3") (pin "A") (pinfunction "A_A") (pintype "passive"))
      (node (ref "R6") (pin "1") (pinfunction "1_1") (pintype "passive"))
    )
    (net (code "35") (name "Net-(LED4-PadA)") (class "Default")
      (node (ref "LED4") (pin "A") (pinfunction "A_A") (pintype "passive"))
      (node (ref "R7") (pin "1") (pinfunction "1_1") (pintype "passive"))
    )
    (net (code "36") (name "Net-(LED5-PadA)") (class "Default")
      (node (ref "LED5") (pin "A") (pinfunction "A_A") (pintype "passive"))
      (node (ref "R8") (pin "1") (pinfunction "1_1") (pintype "passive"))
    )
    (net (code "37") (name "Net-(Q2-PadB)") (class "Default")
      (node (ref "Q2") (pin "B") (pinfunction "B_B") (pintype "passive"))
      (node (ref "R15") (pin "2") (pinfunction "2_2") (pintype "passive"))
    )
    (net (code "38") (name "Net-(Q3-PadB)") (class "Default")
      (node (ref "Q3") (pin "B") (pinfunction "B_B") (pintype "passive"))
      (node (ref "R27") (pin "2") (pinfunction "2_2") (pintype "passive"))
    )
    (net (code "39") (name "Net-(R10-Pad1)") (class "Default")
      (node (ref "R10") (pin "1") (pinfunction "1_1") (pintype "passive"))
      (node (ref "SW4") (pin "L1") (pinfunction "L1_L1") (pintype "passive"))
    )
    (net (code "40") (name "Net-(R23-Pad1)") (class "Default")
      (node (ref "R23") (pin "1") (pinfunction "1_1") (pintype "passive"))
      (node (ref "SW6") (pin "L1") (pinfunction "L1_L1") (pintype "passive"))
    )
    (net (code "41") (name "Net-(UC1-PA4{slash}SPI1_NSS{slash}USART2_CK{slash}ADC12_IN4)") (class "Default")
      (node (ref "R4") (pin "2") (pinfunction "2_2") (pintype "passive"))
      (node (ref "UC1") (pin "14") (pinfunction "PA4/SPI1_NSS/USART2_CK/ADC12_IN4_14") (pintype "bidirectional"))
    )
    (net (code "42") (name "Net-(UC1-PA5{slash}SPI1_SCK{slash}ADC12_IN5)") (class "Default")
      (node (ref "R6") (pin "2") (pinfunction "2_2") (pintype "passive"))
      (node (ref "UC1") (pin "15") (pinfunction "PA5/SPI1_SCK/ADC12_IN5_15") (pintype "bidirectional"))
    )
    (net (code "43") (name "Net-(UC1-PA6{slash}SPI1_MISO{slash}ADC12_IN6{slash}TIM3_CH1)") (class "Default")
      (node (ref "R7") (pin "2") (pinfunction "2_2") (pintype "passive"))
      (node (ref "UC1") (pin "16") (pinfunction "PA6/SPI1_MISO/ADC12_IN6/TIM3_CH1_16") (pintype "bidirectional"))
    )
    (net (code "44") (name "Net-(UC1-PA7{slash}SPI1_MOSI{slash}ADC12_IN7{slash}TIM3_CH2)") (class "Default")
      (node (ref "R8") (pin "2") (pinfunction "2_2") (pintype "passive"))
      (node (ref "UC1") (pin "17") (pinfunction "PA7/SPI1_MOSI/ADC12_IN7/TIM3_CH2_17") (pintype "bidirectional"))
    )
    (net (code "45") (name "Net-(UC1-PB0{slash}ADC12_IN8{slash}TIM3_CH3)") (class "Default")
      (node (ref "R23") (pin "2") (pinfunction "2_2") (pintype "passive"))
      (node (ref "UC1") (pin "18") (pinfunction "PB0/ADC12_IN8/TIM3_CH3_18") (pintype "bidirectional"))
    )
    (net (code "46") (name "Net-(UC1-PB1{slash}ADC12_IN9{slash}TIM3_CH4)") (class "Default")
      (node (ref "R10") (pin "2") (pinfunction "2_2") (pintype "passive"))
      (node (ref "UC1") (pin "19") (pinfunction "PB1/ADC12_IN9/TIM3_CH4_19") (pintype "bidirectional"))
    )
    (net (code "47") (name "Net-(UC1-PB10{slash}I2C2_SCL{slash}USART3_TX)") (class "Default")
      (node (ref "R2") (pin "2") (pinfunction "2_2") (pintype "passive"))
      (node (ref "UC1") (pin "21") (pinfunction "PB10/I2C2_SCL/USART3_TX_21") (pintype "input"))
    )
    (net (code "48") (name "Net-(UC1-PD0-OSC_IN)") (class "Default")
      (node (ref "C7") (pin "2") (pinfunction "2_2") (pintype "passive"))
      (node (ref "Q1") (pin "2") (pinfunction "2_2") (pintype "passive"))
      (node (ref "UC1") (pin "5") (pinfunction "PD0-OSC_IN_5") (pintype "input"))
    )
    (net (code "49") (name "Net-(UC1-PD1-OSC_OUT)") (class "Default")
      (node (ref "C6") (pin "2") (pinfunction "2_2") (pintype "passive"))
      (node (ref "Q1") (pin "1") (pinfunction "1_1") (pintype "passive"))
      (node (ref "UC1") (pin "6") (pinfunction "PD1-OSC_OUT_6") (pintype "input"))
    )
    (net (code "50") (name "POT_1") (class "Default")
      (node (ref "R1") (pin "P$2") (pinfunction "S_P$2") (pintype "passive"))
      (node (ref "UC1") (pin "13") (pinfunction "PA3/USART2_RX/ADC12_IN3/TIM2_CH4_13") (pintype "bidirectional"))
    )
    (net (code "51") (name "POT_2") (class "Default")
      (node (ref "R5") (pin "P$2") (pinfunction "S_P$2") (pintype "passive"))
      (node (ref "UC1") (pin "12") (pinfunction "PA2/USART2_TX/ADC12_IN2/TIM2_CH3_12") (pintype "bidirectional"))
    )
    (net (code "52") (name "POT_3") (class "Default")
      (node (ref "R11") (pin "P$2") (pinfunction "S_P$2") (pintype "passive"))
      (node (ref "UC1") (pin "11") (pinfunction "PA1/USART2_RTS/ADC12_IN1/TIM2_CH2_11") (pintype "bidirectional"))
    )
    (net (code "53") (name "POT_4") (class "Default")
      (node (ref "R21") (pin "P$2") (pinfunction "S_P$2") (pintype "passive"))
      (node (ref "UC1") (pin "10") (pinfunction "PA0_WKUP/USART2_CTS/ADC12_IN0/TIM2_CH1_ETR_10") (pintype "bidirectional"))
    )
    (net (code "54") (name "RESET") (class "Default")
      (node (ref "JP2") (pin "10") (pinfunction "10_10") (pintype "passive"))
      (node (ref "R3") (pin "1") (pinfunction "1_1") (pintype "passive"))
      (node (ref "SW3") (pin "B") (pinfunction "S_B") (pintype "passive"))
      (node (ref "SW3") (pin "B'") (pinfunction "S1_B'") (pintype "passive"))
      (node (ref "UC1") (pin "7") (pinfunction "NRST_7") (pintype "input"))
    )
    (net (code "55") (name "RX") (class "Default")
      (node (ref "JP1") (pin "4") (pinfunction "4_4") (pintype "passive"))
      (node (ref "UC1") (pin "31") (pinfunction "PA10/USART1_RX/TIM1_CH3_31") (pintype "bidirectional"))
    )
    (net (code "56") (name "SW_DUAL") (class "Default")
      (node (ref "SW2") (pin "3") (pinfunction "3_3") (pintype "passive"))
      (node (ref "SW2") (pin "4") (pinfunction "4_4") (pintype "passive"))
      (node (ref "UC1") (pin "3") (pinfunction "PC14-OSC32_IN_3") (pintype "input"))
    )
    (net (code "57") (name "SW_MODE") (class "Default")
      (node (ref "SW1") (pin "3") (pinfunction "3_3") (pintype "passive"))
      (node (ref "SW1") (pin "4") (pinfunction "4_4") (pintype "passive"))
      (node (ref "UC1") (pin "2") (pinfunction "PC13-TAMPER-RTC_2") (pintype "input"))
    )
    (net (code "58") (name "SW_TRIG_1") (class "Default")
      (node (ref "SW6") (pin "P2") (pinfunction "A2_P2") (pintype "passive"))
      (node (ref "SW6") (pin "P5") (pinfunction "B2_P5") (pintype "passive"))
      (node (ref "UC1") (pin "40") (pinfunction "PB4/NJTRST_40") (pintype "bidirectional"))
    )
    (net (code "59") (name "SW_TRIG_2") (class "Default")
      (node (ref "SW4") (pin "P2") (pinfunction "A2_P2") (pintype "passive"))
      (node (ref "SW4") (pin "P5") (pinfunction "B2_P5") (pintype "passive"))
      (node (ref "UC1") (pin "29") (pinfunction "PA8/USART1_CK/TIM1_CH1/MCO_29") (pintype "bidirectional"))
    )
    (net (code "60") (name "TRIG_1") (class "Default")
      (node (ref "Q3") (pin "C") (pinfunction "C_C") (pintype "passive"))
      (node (ref "R28") (pin "1") (pinfunction "1_1") (pintype "passive"))
      (node (ref "UC1") (pin "33") (pinfunction "PA12/USART1_RTS/CAN_TX/TIM1_ETR/USBDP_33") (pintype "bidirectional"))
    )
    (net (code "61") (name "TRIG_2") (class "Default")
      (node (ref "Q2") (pin "C") (pinfunction "C_C") (pintype "passive"))
      (node (ref "R16") (pin "1") (pinfunction "1_1") (pintype "passive"))
      (node (ref "UC1") (pin "22") (pinfunction "PB11/I2C2_SDA/USART3_RX_22") (pintype "input"))
    )
    (net (code "62") (name "TX") (class "Default")
      (node (ref "JP1") (pin "5") (pinfunction "5_5") (pintype "passive"))
      (node (ref "UC1") (pin "30") (pinfunction "PA9/USART1_TX/TIM1_CH2_30") (pintype "input"))
    )
    (net (code "63") (name "VCC") (class "Default")
      (node (ref "C16") (pin "1") (pinfunction "1_1") (pintype "passive"))
      (node (ref "C2") (pin "+") (pinfunction "+_+") (pintype "passive"))
      (node (ref "C21") (pin "1") (pinfunction "1_1") (pintype "passive"))
      (node (ref "D1") (pin "C") (pinfunction "C_C") (pintype "passive"))
      (node (ref "IC1") (pin "3") (pinfunction "VIN_3") (pintype "input"))
      (node (ref "IC4") (pin "8") (pinfunction "V+_8") (pintype "power_in"))
      (node (ref "IC5") (pin "8") (pinfunction "V+_8") (pintype "power_in"))
    )
    (net (code "64") (name "VEE") (class "Default")
      (node (ref "C1") (pin "-") (pinfunction "-_-") (pintype "passive"))
      (node (ref "C18") (pin "2") (pinfunction "2_2") (pintype "passive"))
      (node (ref "C24") (pin "2") (pinfunction "2_2") (pintype "passive"))
      (node (ref "D2") (pin "A") (pinfunction "A_A") (pintype "passive"))
      (node (ref "IC4") (pin "4") (pinfunction "V-_4") (pintype "power_in"))
      (node (ref "IC5") (pin "4") (pinfunction "V-_4") (pintype "power_in"))
      (node (ref "R25") (pin "1") (pinfunction "1_1") (pintype "passive"))
    )
    (net (code "65") (name "unconnected-(J3-2-PadP2)") (class "Default")
      (node (ref "J3") (pin "P2") (pinfunction "2_P2") (pintype "passive"))
    )
    (net (code "66") (name "unconnected-(J4-2-PadP2)") (class "Default")
      (node (ref "J4") (pin "P2") (pinfunction "2_P2") (pintype "passive"))
    )
    (net (code "67") (name "unconnected-(JP1-Pad2)") (class "Default")
      (node (ref "JP1") (pin "2") (pinfunction "2_2") (pintype "passive"))
    )
    (net (code "68") (name "unconnected-(JP1-Pad3)") (class "Default")
      (node (ref "JP1") (pin "3") (pinfunction "3_3") (pintype "passive"))
    )
    (net (code "69") (name "unconnected-(JP1-Pad6)") (class "Default")
      (node (ref "JP1") (pin "6") (pinfunction "6_6") (pintype "passive"))
    )
    (net (code "70") (name "unconnected-(JP2-Pad7)") (class "Default")
      (node (ref "JP2") (pin "7") (pinfunction "7_7") (pintype "passive"))
    )
    (net (code "71") (name "unconnected-(SW4A-A1-PadP1)") (class "Default")
      (node (ref "SW4") (pin "P1") (pinfunction "A1_P1") (pintype "passive"))
    )
    (net (code "72") (name "unconnected-(SW4A-B1-PadP4)") (class "Default")
      (node (ref "SW4") (pin "P4") (pinfunction "B1_P4") (pintype "passive"))
    )
    (net (code "73") (name "unconnected-(SW6A-A1-PadP1)") (class "Default")
      (node (ref "SW6") (pin "P1") (pinfunction "A1_P1") (pintype "passive"))
    )
    (net (code "74") (name "unconnected-(SW6A-B1-PadP4)") (class "Default")
      (node (ref "SW6") (pin "P4") (pinfunction "B1_P4") (pintype "passive"))
    )
    (net (code "75") (name "unconnected-(UC1-PA11{slash}USART1_CTS{slash}CAN_RX{slash}TIM1_CH4{slash}USBDM-Pad32)") (class "Default")
      (node (ref "UC1") (pin "32") (pinfunction "PA11/USART1_CTS/CAN_RX/TIM1_CH4/USBDM_32") (pintype "bidirectional"))
    )
    (net (code "76") (name "unconnected-(UC1-PB5{slash}I2C1_SMBA-Pad41)") (class "Default")
      (node (ref "UC1") (pin "41") (pinfunction "PB5/I2C1_SMBA_41") (pintype "input"))
    )
    (net (code "77") (name "unconnected-(UC1-PB6{slash}I2C1_SCL{slash}TIM4_CH1-Pad42)") (class "Default")
      (node (ref "UC1") (pin "42") (pinfunction "PB6/I2C1_SCL/TIM4_CH1_42") (pintype "input"))
    )
    (net (code "78") (name "unconnected-(UC1-PB7{slash}I2C1_SDA{slash}TIM4_CH2-Pad43)") (class "Default")
      (node (ref "UC1") (pin "43") (pinfunction "PB7/I2C1_SDA/TIM4_CH2_43") (pintype "bidirectional"))
    )
    (net (code "79") (name "unconnected-(UC1-PB8{slash}TIM4_CH3-Pad45)") (class "Default")
      (node (ref "UC1") (pin "45") (pinfunction "PB8/TIM4_CH3_45") (pintype "bidirectional"))
    )
    (net (code "80") (name "unconnected-(UC1-PB14{slash}SPI2_MISO{slash}USART3_RTS{slash}TIM1_CH2N-Pad27)") (class "Default")
      (node (ref "UC1") (pin "27") (pinfunction "PB14/SPI2_MISO/USART3_RTS/TIM1_CH2N_27") (pintype "input"))
    )
    (net (code "81") (name "unconnected-(UC1-PC15-OSC32_OUT-Pad4)") (class "Default")
      (node (ref "UC1") (pin "4") (pinfunction "PC15-OSC32_OUT_4") (pintype "input"))
    )
  )
)
